# CLK_ICS307-02_PLL.net
KiCad netlist of a schematic drawn in Altium Designer
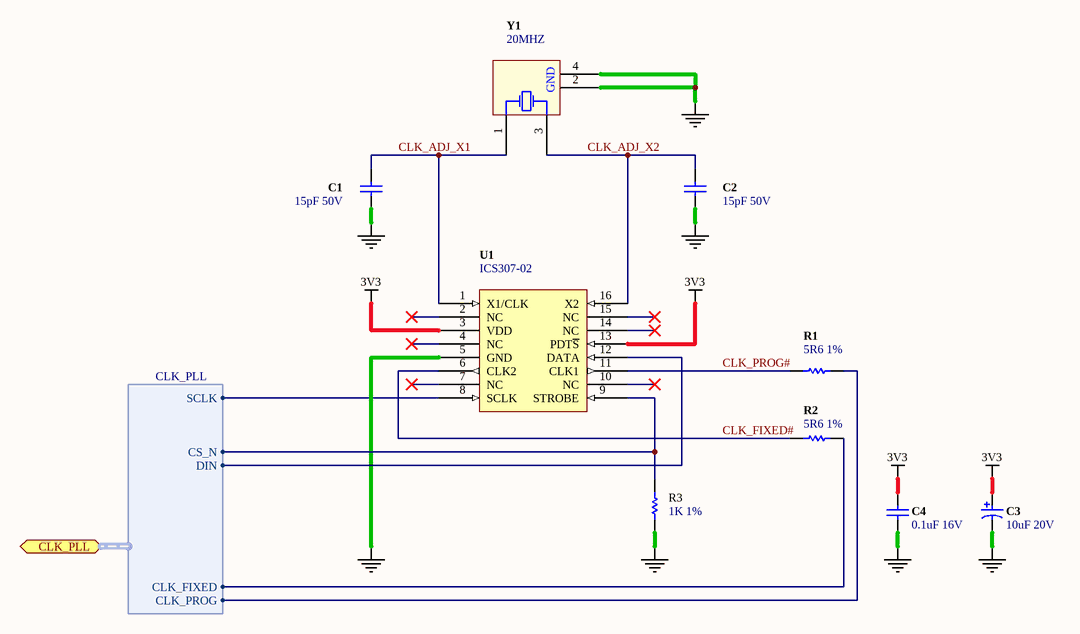
[diagram p0: CLK_ICS307-02_PLL.SchDoc]

(export (version "E")
  (design (tool "Eeschema 10.0.6"))
  (components
    (comp (ref "C1")
      (value "15pF 50V")
      (footprint "CAPC1005-STAR")
      (description "Capacitor, Ceramic, 15pF 5% 50V 0402 (1005)")
      (fields (field (name "TOLERANCE") "5 %"))
      (libsource (lib "altium-import") (part "root_0_CAP-NP_"))
    )
    (comp (ref "C2")
      (value "15pF 50V")
      (footprint "CAPC1005-STAR")
      (description "Capacitor, Ceramic, 15pF 5% 50V 0402 (1005)")
      (fields (field (name "TOLERANCE") "5 %"))
      (libsource (lib "altium-import") (part "root_0_CAP-NP_"))
    )
    (comp (ref "C3")
      (value "10uF 20V")
      (footprint "CAPC3528-STAR")
      (description "Capacitor, Tantalum, 10uF 10% 20V MCCT-B (3528)")
      (fields (field (name "TOLERANCE") "10 %"))
      (libsource (lib "altium-import") (part "root_0_CAP-P_"))
    )
    (comp (ref "C4")
      (value "0.1uF 16V")
      (footprint "CAPC1005-STAR")
      (description "Capacitor, Ceramic, 0.1uF 10% 16V 0402 (1005) X7R")
      (fields (field (name "TOLERANCE") "10 %"))
      (libsource (lib "altium-import") (part "root_0_CAP-NP_"))
    )
    (comp (ref "R1")
      (value "5R6 1%")
      (footprint "RESC1005-STAR")
      (description "Resistor, 5R6 1% 0402 (1005)")
      (fields (field (name "TOLERANCE") "1 %"))
      (libsource (lib "altium-import") (part "root_3_RES_"))
    )
    (comp (ref "R2")
      (value "5R6 1%")
      (footprint "RESC1005-STAR")
      (description "Resistor, 5R6 1% 0402 (1005)")
      (fields (field (name "TOLERANCE") "1 %"))
      (libsource (lib "altium-import") (part "root_3_RES_"))
    )
    (comp (ref "R3")
      (value "1K 1%")
      (footprint "RESC1005-STAR")
      (description "Resistor, 1K 1% 0402 (1005)")
      (fields (field (name "TOLERANCE") "1 %"))
      (libsource (lib "altium-import") (part "root_0_RES_"))
    )
    (comp (ref "U1")
      (value "ICS307-02")
      (footprint "SOIC127P600-16")
      (description "ICS307-02, SPI Programmable Clock Generator")
      (libsource (lib "altium-import") (part "root_0_ICS307_"))
    )
    (comp (ref "Y1")
      (value "20MHZ")
      (footprint "XTAL-200X126-4")
      (description "Crystal, SMD, 20.000000MHz Stab=30ppm 20.0pF")
      (libsource (lib "altium-import") (part "root_1_CRYSTAL-200X126-4_"))
    )
  )
  (nets
    (net (code "2") (name "/CLK_ADJ_X1") (class "Default")
      (node (ref "C1") (pin "1") (pinfunction "1_1") (pintype "passive"))
      (node (ref "U1") (pin "1") (pinfunction "X1/CLK_1") (pintype "input"))
      (node (ref "Y1") (pin "1") (pinfunction "X1_1") (pintype "passive"))
    )
    (net (code "3") (name "/CLK_ADJ_X2") (class "Default")
      (node (ref "C2") (pin "1") (pinfunction "1_1") (pintype "passive"))
      (node (ref "U1") (pin "16") (pinfunction "X2_16") (pintype "input"))
      (node (ref "Y1") (pin "3") (pinfunction "X2_3") (pintype "passive"))
    )
    (net (code "4") (name "/CLK_FIXED") (class "Default")
      (node (ref "R2") (pin "1") (pinfunction "1_1") (pintype "passive"))
    )
    (net (code "5") (name "/CLK_FIXED#") (class "Default")
      (node (ref "R2") (pin "2") (pinfunction "2_2") (pintype "passive"))
      (node (ref "U1") (pin "6") (pinfunction "CLK2_6") (pintype "output"))
    )
    (net (code "6") (name "/CLK_PROG") (class "Default")
      (node (ref "R1") (pin "1") (pinfunction "1_1") (pintype "passive"))
    )
    (net (code "7") (name "/CLK_PROG#") (class "Default")
      (node (ref "R1") (pin "2") (pinfunction "2_2") (pintype "passive"))
      (node (ref "U1") (pin "11") (pinfunction "CLK1_11") (pintype "output"))
    )
    (net (code "8") (name "/CS_N") (class "Default")
      (node (ref "R3") (pin "1") (pinfunction "1_1") (pintype "passive"))
      (node (ref "U1") (pin "9") (pinfunction "STROBE_9") (pintype "input"))
    )
    (net (code "9") (name "/DIN") (class "Default")
      (node (ref "U1") (pin "12") (pinfunction "DATA_12") (pintype "input"))
    )
    (net (code "10") (name "/SCLK") (class "Default")
      (node (ref "U1") (pin "8") (pinfunction "SCLK_8") (pintype "input"))
    )
    (net (code "12") (name "3V3") (class "Default")
      (node (ref "C3") (pin "1") (pinfunction "1_1") (pintype "passive"))
      (node (ref "C4") (pin "1") (pinfunction "1_1") (pintype "passive"))
      (node (ref "U1") (pin "13") (pinfunction "PDT~{S}_13") (pintype "input"))
      (node (ref "U1") (pin "3") (pinfunction "VDD_3") (pintype "power_in"))
    )
    (net (code "13") (name "GND") (class "Default")
      (node (ref "C1") (pin "2") (pinfunction "2_2") (pintype "passive"))
      (node (ref "C2") (pin "2") (pinfunction "2_2") (pintype "passive"))
      (node (ref "C3") (pin "2") (pinfunction "2_2") (pintype "passive"))
      (node (ref "C4") (pin "2") (pinfunction "2_2") (pintype "passive"))
      (node (ref "R3") (pin "2") (pinfunction "2_2") (pintype "passive"))
      (node (ref "U1") (pin "5") (pinfunction "GND_5") (pintype "power_in"))
      (node (ref "Y1") (pin "2") (pinfunction "GND_2") (pintype "passive"))
      (node (ref "Y1") (pin "4") (pinfunction "GND_4") (pintype "passive"))
    )
    (net (code "14") (name "unconnected-(U1-NC-Pad2)") (class "Default")
      (node (ref "U1") (pin "2") (pinfunction "NC_2") (pintype "passive+no_connect"))
    )
    (net (code "15") (name "unconnected-(U1-NC-Pad4)") (class "Default")
      (node (ref "U1") (pin "4") (pinfunction "NC_4") (pintype "passive+no_connect"))
    )
    (net (code "16") (name "unconnected-(U1-NC-Pad7)") (class "Default")
      (node (ref "U1") (pin "7") (pinfunction "NC_7") (pintype "passive+no_connect"))
    )
    (net (code "17") (name "unconnected-(U1-NC-Pad10)") (class "Default")
      (node (ref "U1") (pin "10") (pinfunction "NC_10") (pintype "passive+no_connect"))
    )
    (net (code "18") (name "unconnected-(U1-NC-Pad14)") (class "Default")
      (node (ref "U1") (pin "14") (pinfunction "NC_14") (pintype "passive+no_connect"))
    )
    (net (code "19") (name "unconnected-(U1-NC-Pad15)") (class "Default")
      (node (ref "U1") (pin "15") (pinfunction "NC_15") (pintype "passive+no_connect"))
    )
  )
)
